# voice_caller.net
KiCad netlist of a schematic drawn in EAGLE
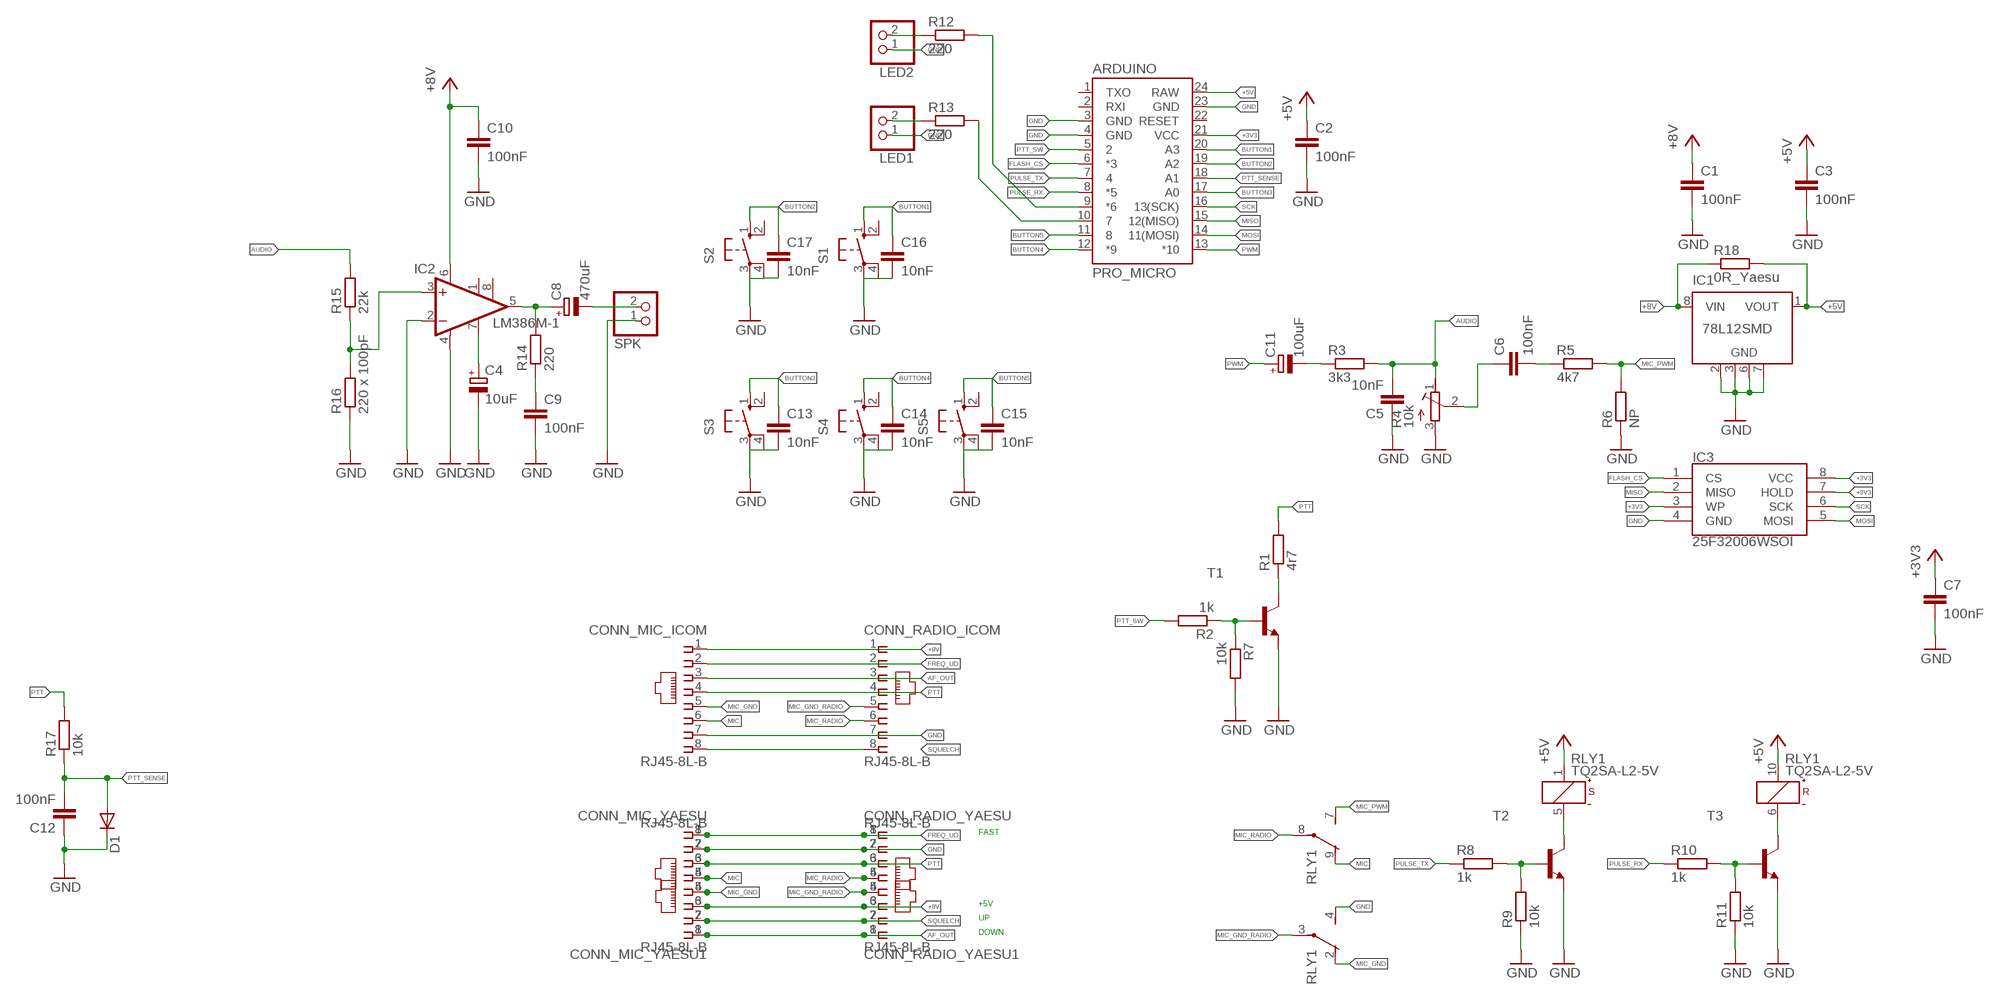
[diagram p0: schematic, sheet 1]

(export (version "E")
  (design (tool "Eeschema 10.0.6"))
  (components
    (comp (ref "ARDUINO")
      (value "PRO_MICRO")
      (footprint "eagle-import:SPARKFUN_PRO_MICRO")
      (libsource (lib "eagle-import") (part "SPARKFUN_PRO_MICRO"))
    )
    (comp (ref "C1")
      (value "100nF")
      (footprint "eagle-import:C1206K")
      (libsource (lib "eagle-import") (part "C-EUC1206K"))
    )
    (comp (ref "C2")
      (value "100nF")
      (footprint "eagle-import:C1206K")
      (libsource (lib "eagle-import") (part "C-EUC1206K"))
    )
    (comp (ref "C3")
      (value "100nF")
      (footprint "eagle-import:C1206K")
      (libsource (lib "eagle-import") (part "C-EUC1206K"))
    )
    (comp (ref "C4")
      (value "10uF")
      (footprint "eagle-import:E2,5-6")
      (libsource (lib "eagle-import") (part "CPOL-EUE2.5-6"))
    )
    (comp (ref "C5")
      (value "10nF")
      (footprint "eagle-import:C1206K")
      (libsource (lib "eagle-import") (part "C-EUC1206K"))
    )
    (comp (ref "C6")
      (value "100nF")
      (footprint "eagle-import:C1206K")
      (libsource (lib "eagle-import") (part "C-EUC1206K"))
    )
    (comp (ref "C7")
      (value "100nF")
      (footprint "eagle-import:C1206K")
      (libsource (lib "eagle-import") (part "C-EUC1206K"))
    )
    (comp (ref "C8")
      (value "470uF")
      (footprint "eagle-import:E2,5-6")
      (libsource (lib "eagle-import") (part "CPOL-EUE2.5-6"))
    )
    (comp (ref "C9")
      (value "100nF")
      (footprint "eagle-import:C1206K")
      (libsource (lib "eagle-import") (part "C-EUC1206K"))
    )
    (comp (ref "C10")
      (value "100nF")
      (footprint "eagle-import:C1206K")
      (libsource (lib "eagle-import") (part "C-EUC1206K"))
    )
    (comp (ref "C11")
      (value "100uF")
      (footprint "eagle-import:E2,5-6")
      (libsource (lib "eagle-import") (part "CPOL-EUE2.5-6"))
    )
    (comp (ref "C12")
      (value "100nF")
      (footprint "eagle-import:C1206K")
      (libsource (lib "eagle-import") (part "C-EUC1206K"))
    )
    (comp (ref "C13")
      (value "10nF")
      (footprint "eagle-import:C1206K")
      (libsource (lib "eagle-import") (part "C-EUC1206K"))
    )
    (comp (ref "C14")
      (value "10nF")
      (footprint "eagle-import:C1206K")
      (libsource (lib "eagle-import") (part "C-EUC1206K"))
    )
    (comp (ref "C15")
      (value "10nF")
      (footprint "eagle-import:C1206K")
      (libsource (lib "eagle-import") (part "C-EUC1206K"))
    )
    (comp (ref "C16")
      (value "10nF")
      (footprint "eagle-import:C1206K")
      (libsource (lib "eagle-import") (part "C-EUC1206K"))
    )
    (comp (ref "C17")
      (value "10nF")
      (footprint "eagle-import:C1206K")
      (libsource (lib "eagle-import") (part "C-EUC1206K"))
    )
    (comp (ref "CONN_MIC_ICOM")
      (value "RJ45-8L-B")
      (footprint "eagle-import:RJ45-NO-SHIELD")
      (fields (field (name "MF") "TYCO ELECTRONICS"))
      (libsource (lib "eagle-import") (part "RJ45-8L-B"))
    )
    (comp (ref "CONN_MIC_YAESU")
      (value "RJ45-8L-B")
      (footprint "eagle-import:RJ45-NO-SHIELD")
      (fields (field (name "MF") "TYCO ELECTRONICS"))
      (libsource (lib "eagle-import") (part "RJ45-8L-B"))
    )
    (comp (ref "CONN_MIC_YAESU1")
      (value "RJ45-8L-B")
      (footprint "eagle-import:RJ45-NO-SHIELD")
      (fields (field (name "MF") "TYCO ELECTRONICS"))
      (libsource (lib "eagle-import") (part "RJ45-8L-B"))
    )
    (comp (ref "CONN_RADIO_ICOM")
      (value "RJ45-8L-B")
      (footprint "eagle-import:RJ45-NO-SHIELD")
      (fields (field (name "MF") "TYCO ELECTRONICS"))
      (libsource (lib "eagle-import") (part "RJ45-8L-B"))
    )
    (comp (ref "CONN_RADIO_YAESU")
      (value "RJ45-8L-B")
      (footprint "eagle-import:RJ45-NO-SHIELD")
      (fields (field (name "MF") "TYCO ELECTRONICS"))
      (libsource (lib "eagle-import") (part "RJ45-8L-B"))
    )
    (comp (ref "CONN_RADIO_YAESU1")
      (value "RJ45-8L-B")
      (footprint "eagle-import:RJ45-NO-SHIELD")
      (fields (field (name "MF") "TYCO ELECTRONICS"))
      (libsource (lib "eagle-import") (part "RJ45-8L-B"))
    )
    (comp (ref "D1")
      (value "DIODE-SOD80C")
      (footprint "eagle-import:SOD80C")
      (libsource (lib "eagle-import") (part "DIODE-SOD80C"))
    )
    (comp (ref "IC1")
      (value "78L12SMD")
      (footprint "eagle-import:SO08")
      (libsource (lib "eagle-import") (part "78LSMD12"))
    )
    (comp (ref "IC2")
      (value "LM386M-1")
      (footprint "eagle-import:SO08")
      (libsource (lib "eagle-import") (part "LM386?-M1"))
    )
    (comp (ref "IC3")
      (value "25F32006WSOI")
      (footprint "eagle-import:SO08-EIAJ")
      (libsource (lib "eagle-import") (part "SPI_FLASH-X25XXSMD1"))
    )
    (comp (ref "LED1")
      (value "PINHD-1X2")
      (footprint "eagle-import:1X02")
      (libsource (lib "eagle-import") (part "PINHD-1X2"))
    )
    (comp (ref "LED2")
      (value "PINHD-1X2")
      (footprint "eagle-import:1X02")
      (libsource (lib "eagle-import") (part "PINHD-1X2"))
    )
    (comp (ref "R1")
      (value "4r7")
      (footprint "eagle-import:M1206")
      (libsource (lib "eagle-import") (part "R-EU_M1206"))
    )
    (comp (ref "R2")
      (value "1k")
      (footprint "eagle-import:M1206")
      (libsource (lib "eagle-import") (part "R-EU_M1206"))
    )
    (comp (ref "R3")
      (value "3k3")
      (footprint "eagle-import:M1206")
      (libsource (lib "eagle-import") (part "R-EU_M1206"))
    )
    (comp (ref "R4")
      (value "10k")
      (footprint "eagle-import:RTRIMT93XB")
      (libsource (lib "eagle-import") (part "R-TRIMMT93XB"))
    )
    (comp (ref "R5")
      (value "4k7")
      (footprint "eagle-import:M1206")
      (libsource (lib "eagle-import") (part "R-EU_M1206"))
    )
    (comp (ref "R6")
      (value "NP")
      (footprint "eagle-import:M1206")
      (libsource (lib "eagle-import") (part "R-EU_M1206"))
    )
    (comp (ref "R7")
      (value "10k")
      (footprint "eagle-import:M1206")
      (libsource (lib "eagle-import") (part "R-EU_M1206"))
    )
    (comp (ref "R8")
      (value "1k")
      (footprint "eagle-import:M1206")
      (libsource (lib "eagle-import") (part "R-EU_M1206"))
    )
    (comp (ref "R9")
      (value "10k")
      (footprint "eagle-import:M1206")
      (libsource (lib "eagle-import") (part "R-EU_M1206"))
    )
    (comp (ref "R10")
      (value "1k")
      (footprint "eagle-import:M1206")
      (libsource (lib "eagle-import") (part "R-EU_M1206"))
    )
    (comp (ref "R11")
      (value "10k")
      (footprint "eagle-import:M1206")
      (libsource (lib "eagle-import") (part "R-EU_M1206"))
    )
    (comp (ref "R12")
      (value "220")
      (footprint "eagle-import:M1206")
      (libsource (lib "eagle-import") (part "R-EU_M1206"))
    )
    (comp (ref "R13")
      (value "220")
      (footprint "eagle-import:M1206")
      (libsource (lib "eagle-import") (part "R-EU_M1206"))
    )
    (comp (ref "R14")
      (value "220")
      (footprint "eagle-import:M1206")
      (libsource (lib "eagle-import") (part "R-EU_M1206"))
    )
    (comp (ref "R15")
      (value "22k")
      (footprint "eagle-import:M1206")
      (libsource (lib "eagle-import") (part "R-EU_M1206"))
    )
    (comp (ref "R16")
      (value "220 x 100pF")
      (footprint "eagle-import:M1206")
      (libsource (lib "eagle-import") (part "R-EU_M1206"))
    )
    (comp (ref "R17")
      (value "10k")
      (footprint "eagle-import:M1206")
      (libsource (lib "eagle-import") (part "R-EU_M1206"))
    )
    (comp (ref "R18")
      (value "0R_Yaesu")
      (footprint "eagle-import:M1206")
      (libsource (lib "eagle-import") (part "R-EU_M1206"))
    )
    (comp (ref "RLY1")
      (value "TQ2SA-L2-5V")
      (footprint "eagle-import:TQ-SA")
      (fields (field (name "MF") "AROMAT/ MATSUSHITA"))
      (libsource (lib "eagle-import") (part "TQ2?-L2-SA5V"))
    )
    (comp (ref "S1")
      (value "10-XX")
      (footprint "eagle-import:B3F-10XX")
      (fields (field (name "MPN") "B3F-1000"))
      (libsource (lib "eagle-import") (part "10-XX"))
    )
    (comp (ref "S2")
      (value "10-XX")
      (footprint "eagle-import:B3F-10XX")
      (fields (field (name "MPN") "B3F-1000"))
      (libsource (lib "eagle-import") (part "10-XX"))
    )
    (comp (ref "S3")
      (value "10-XX")
      (footprint "eagle-import:B3F-10XX")
      (fields (field (name "MPN") "B3F-1000"))
      (libsource (lib "eagle-import") (part "10-XX"))
    )
    (comp (ref "S4")
      (value "10-XX")
      (footprint "eagle-import:B3F-10XX")
      (fields (field (name "MPN") "B3F-1000"))
      (libsource (lib "eagle-import") (part "10-XX"))
    )
    (comp (ref "S5")
      (value "10-XX")
      (footprint "eagle-import:B3F-10XX")
      (fields (field (name "MPN") "B3F-1000"))
      (libsource (lib "eagle-import") (part "10-XX"))
    )
    (comp (ref "SPK")
      (value "PINHD-1X2")
      (footprint "eagle-import:1X02")
      (libsource (lib "eagle-import") (part "PINHD-1X2"))
    )
    (comp (ref "T1")
      (value "MMBT3904LT1-NPN-SOT23-BEC")
      (footprint "eagle-import:SOT23-BEC")
      (libsource (lib "eagle-import") (part "-NPN-SOT23-BECMMBT3904LT1"))
    )
    (comp (ref "T2")
      (value "MMBT3904LT1-NPN-SOT23-BEC")
      (footprint "eagle-import:SOT23-BEC")
      (libsource (lib "eagle-import") (part "-NPN-SOT23-BECMMBT3904LT1"))
    )
    (comp (ref "T3")
      (value "MMBT3904LT1-NPN-SOT23-BEC")
      (footprint "eagle-import:SOT23-BEC")
      (libsource (lib "eagle-import") (part "-NPN-SOT23-BECMMBT3904LT1"))
    )
  )
  (nets
    (net (code "1") (name "+3V3") (class "Default")
      (node (ref "ARDUINO") (pin "21") (pinfunction "VCC_21") (pintype "power_in"))
      (node (ref "C7") (pin "1") (pinfunction "1_1") (pintype "passive"))
      (node (ref "IC3") (pin "3") (pinfunction "WP_3") (pintype "bidirectional"))
      (node (ref "IC3") (pin "7") (pinfunction "HOLD_7") (pintype "bidirectional"))
      (node (ref "IC3") (pin "8") (pinfunction "VCC_8") (pintype "power_in"))
    )
    (net (code "2") (name "+5V") (class "Default")
      (node (ref "ARDUINO") (pin "24") (pinfunction "RAW_24") (pintype "power_in"))
      (node (ref "C2") (pin "1") (pinfunction "1_1") (pintype "passive"))
      (node (ref "C3") (pin "1") (pinfunction "1_1") (pintype "passive"))
      (node (ref "IC1") (pin "1") (pinfunction "VOUT_1") (pintype "output"))
      (node (ref "R18") (pin "2") (pinfunction "2_2") (pintype "passive"))
      (node (ref "RLY1") (pin "1") (pinfunction "+_1") (pintype "passive"))
      (node (ref "RLY1") (pin "10") (pinfunction "+_10") (pintype "passive"))
    )
    (net (code "3") (name "+8V") (class "Default")
      (node (ref "C1") (pin "1") (pinfunction "1_1") (pintype "passive"))
      (node (ref "C10") (pin "1") (pinfunction "1_1") (pintype "passive"))
      (node (ref "CONN_MIC_ICOM") (pin "1") (pinfunction "1_1") (pintype "passive"))
      (node (ref "CONN_MIC_YAESU") (pin "6") (pinfunction "6_6") (pintype "passive"))
      (node (ref "CONN_MIC_YAESU1") (pin "3") (pinfunction "3_3") (pintype "passive"))
      (node (ref "CONN_RADIO_ICOM") (pin "1") (pinfunction "1_1") (pintype "passive"))
      (node (ref "CONN_RADIO_YAESU") (pin "6") (pinfunction "6_6") (pintype "passive"))
      (node (ref "CONN_RADIO_YAESU1") (pin "3") (pinfunction "3_3") (pintype "passive"))
      (node (ref "IC1") (pin "8") (pinfunction "VIN_8") (pintype "passive"))
      (node (ref "IC2") (pin "6") (pinfunction "VS_6") (pintype "power_in"))
      (node (ref "R18") (pin "1") (pinfunction "1_1") (pintype "passive"))
    )
    (net (code "4") (name "AF_OUT") (class "Default")
      (node (ref "CONN_MIC_ICOM") (pin "3") (pinfunction "3_3") (pintype "passive"))
      (node (ref "CONN_MIC_YAESU") (pin "8") (pinfunction "8_8") (pintype "passive"))
      (node (ref "CONN_MIC_YAESU1") (pin "1") (pinfunction "1_1") (pintype "passive"))
      (node (ref "CONN_RADIO_ICOM") (pin "3") (pinfunction "3_3") (pintype "passive"))
      (node (ref "CONN_RADIO_YAESU") (pin "8") (pinfunction "8_8") (pintype "passive"))
      (node (ref "CONN_RADIO_YAESU1") (pin "1") (pinfunction "1_1") (pintype "passive"))
    )
    (net (code "5") (name "AUDIO") (class "Default")
      (node (ref "C5") (pin "2") (pinfunction "2_2") (pintype "passive"))
      (node (ref "R15") (pin "2") (pinfunction "2_2") (pintype "passive"))
      (node (ref "R3") (pin "2") (pinfunction "2_2") (pintype "passive"))
      (node (ref "R4") (pin "1") (pinfunction "E_1") (pintype "passive"))
    )
    (net (code "6") (name "BUTTON1") (class "Default")
      (node (ref "ARDUINO") (pin "20") (pinfunction "A3_20") (pintype "bidirectional"))
      (node (ref "C16") (pin "1") (pinfunction "1_1") (pintype "passive"))
      (node (ref "S1") (pin "1") (pinfunction "S_1") (pintype "passive"))
    )
    (net (code "7") (name "BUTTON2") (class "Default")
      (node (ref "ARDUINO") (pin "19") (pinfunction "A2_19") (pintype "bidirectional"))
      (node (ref "C17") (pin "1") (pinfunction "1_1") (pintype "passive"))
      (node (ref "S2") (pin "1") (pinfunction "S_1") (pintype "passive"))
    )
    (net (code "8") (name "BUTTON3") (class "Default")
      (node (ref "ARDUINO") (pin "17") (pinfunction "A0_17") (pintype "bidirectional"))
      (node (ref "C13") (pin "1") (pinfunction "1_1") (pintype "passive"))
      (node (ref "S3") (pin "1") (pinfunction "S_1") (pintype "passive"))
    )
    (net (code "9") (name "BUTTON4") (class "Default")
      (node (ref "ARDUINO") (pin "12") (pinfunction "*9_12") (pintype "bidirectional"))
      (node (ref "C14") (pin "1") (pinfunction "1_1") (pintype "passive"))
      (node (ref "S4") (pin "1") (pinfunction "S_1") (pintype "passive"))
    )
    (net (code "10") (name "BUTTON5") (class "Default")
      (node (ref "ARDUINO") (pin "11") (pinfunction "8_11") (pintype "bidirectional"))
      (node (ref "C15") (pin "1") (pinfunction "1_1") (pintype "passive"))
      (node (ref "S5") (pin "1") (pinfunction "S_1") (pintype "passive"))
    )
    (net (code "11") (name "FLASH_CS") (class "Default")
      (node (ref "ARDUINO") (pin "6") (pinfunction "*3_6") (pintype "bidirectional"))
      (node (ref "IC3") (pin "1") (pinfunction "CS_1") (pintype "bidirectional"))
    )
    (net (code "12") (name "FREQ_UD") (class "Default")
      (node (ref "CONN_MIC_ICOM") (pin "2") (pinfunction "2_2") (pintype "passive"))
      (node (ref "CONN_MIC_YAESU") (pin "1") (pinfunction "1_1") (pintype "passive"))
      (node (ref "CONN_MIC_YAESU1") (pin "8") (pinfunction "8_8") (pintype "passive"))
      (node (ref "CONN_RADIO_ICOM") (pin "2") (pinfunction "2_2") (pintype "passive"))
      (node (ref "CONN_RADIO_YAESU") (pin "1") (pinfunction "1_1") (pintype "passive"))
      (node (ref "CONN_RADIO_YAESU1") (pin "8") (pinfunction "8_8") (pintype "passive"))
    )
    (net (code "13") (name "GND") (class "Default")
      (node (ref "ARDUINO") (pin "23") (pinfunction "GND_23") (pintype "power_in"))
      (node (ref "ARDUINO") (pin "3") (pinfunction "GND_3") (pintype "power_in"))
      (node (ref "ARDUINO") (pin "4") (pinfunction "GND_4") (pintype "power_in"))
      (node (ref "C1") (pin "2") (pinfunction "2_2") (pintype "passive"))
      (node (ref "C10") (pin "2") (pinfunction "2_2") (pintype "passive"))
      (node (ref "C12") (pin "1") (pinfunction "1_1") (pintype "passive"))
      (node (ref "C13") (pin "2") (pinfunction "2_2") (pintype "passive"))
      (node (ref "C14") (pin "2") (pinfunction "2_2") (pintype "passive"))
      (node (ref "C15") (pin "2") (pinfunction "2_2") (pintype "passive"))
      (node (ref "C16") (pin "2") (pinfunction "2_2") (pintype "passive"))
      (node (ref "C17") (pin "2") (pinfunction "2_2") (pintype "passive"))
      (node (ref "C2") (pin "2") (pinfunction "2_2") (pintype "passive"))
      (node (ref "C3") (pin "2") (pinfunction "2_2") (pintype "passive"))
      (node (ref "C4") (pin "-") (pinfunction "-_-") (pintype "passive"))
      (node (ref "C5") (pin "1") (pinfunction "1_1") (pintype "passive"))
      (node (ref "C7") (pin "2") (pinfunction "2_2") (pintype "passive"))
      (node (ref "C9") (pin "2") (pinfunction "2_2") (pintype "passive"))
      (node (ref "CONN_MIC_ICOM") (pin "7") (pinfunction "7_7") (pintype "passive"))
      (node (ref "CONN_MIC_YAESU") (pin "2") (pinfunction "2_2") (pintype "passive"))
      (node (ref "CONN_MIC_YAESU1") (pin "7") (pinfunction "7_7") (pintype "passive"))
      (node (ref "CONN_RADIO_ICOM") (pin "7") (pinfunction "7_7") (pintype "passive"))
      (node (ref "CONN_RADIO_YAESU") (pin "2") (pinfunction "2_2") (pintype "passive"))
      (node (ref "CONN_RADIO_YAESU1") (pin "7") (pinfunction "7_7") (pintype "passive"))
      (node (ref "D1") (pin "C") (pinfunction "C_C") (pintype "passive"))
      (node (ref "IC1") (pin "2") (pinfunction "GND_2") (pintype "power_in"))
      (node (ref "IC1") (pin "3") (pinfunction "GND_3") (pintype "power_in"))
      (node (ref "IC1") (pin "6") (pinfunction "GND_6") (pintype "power_in"))
      (node (ref "IC1") (pin "7") (pinfunction "GND_7") (pintype "power_in"))
      (node (ref "IC2") (pin "2") (pinfunction "-IN_2") (pintype "input"))
      (node (ref "IC2") (pin "4") (pinfunction "GND_4") (pintype "power_in"))
      (node (ref "IC3") (pin "4") (pinfunction "GND_4") (pintype "power_in"))
      (node (ref "LED1") (pin "1") (pinfunction "1_1") (pintype "passive"))
      (node (ref "LED2") (pin "1") (pinfunction "1_1") (pintype "passive"))
      (node (ref "R11") (pin "1") (pinfunction "1_1") (pintype "passive"))
      (node (ref "R16") (pin "1") (pinfunction "1_1") (pintype "passive"))
      (node (ref "R4") (pin "3") (pinfunction "A_3") (pintype "passive"))
      (node (ref "R6") (pin "1") (pinfunction "1_1") (pintype "passive"))
      (node (ref "R7") (pin "2") (pinfunction "2_2") (pintype "passive"))
      (node (ref "R9") (pin "1") (pinfunction "1_1") (pintype "passive"))
      (node (ref "RLY1") (pin "4") (pinfunction "S_4") (pintype "passive"))
      (node (ref "S1") (pin "3") (pinfunction "P_3") (pintype "passive"))
      (node (ref "S1") (pin "4") (pinfunction "P1_4") (pintype "passive"))
      (node (ref "S2") (pin "3") (pinfunction "P_3") (pintype "passive"))
      (node (ref "S2") (pin "4") (pinfunction "P1_4") (pintype "passive"))
      (node (ref "S3") (pin "3") (pinfunction "P_3") (pintype "passive"))
      (node (ref "S3") (pin "4") (pinfunction "P1_4") (pintype "passive"))
      (node (ref "S4") (pin "3") (pinfunction "P_3") (pintype "passive"))
      (node (ref "S4") (pin "4") (pinfunction "P1_4") (pintype "passive"))
      (node (ref "S5") (pin "3") (pinfunction "P_3") (pintype "passive"))
      (node (ref "S5") (pin "4") (pinfunction "P1_4") (pintype "passive"))
      (node (ref "SPK") (pin "1") (pinfunction "1_1") (pintype "passive"))
      (node (ref "T1") (pin "E") (pinfunction "E_E") (pintype "passive"))
      (node (ref "T2") (pin "E") (pinfunction "E_E") (pintype "passive"))
      (node (ref "T3") (pin "E") (pinfunction "E_E") (pintype "passive"))
    )
    (net (code "14") (name "MIC") (class "Default")
      (node (ref "CONN_MIC_ICOM") (pin "6") (pinfunction "6_6") (pintype "passive"))
      (node (ref "CONN_MIC_YAESU") (pin "4") (pinfunction "4_4") (pintype "passive"))
      (node (ref "CONN_MIC_YAESU1") (pin "5") (pinfunction "5_5") (pintype "passive"))
      (node (ref "RLY1") (pin "9") (pinfunction "O_9") (pintype "passive"))
    )
    (net (code "15") (name "MIC_GND") (class "Default")
      (node (ref "CONN_MIC_ICOM") (pin "5") (pinfunction "5_5") (pintype "passive"))
      (node (ref "CONN_MIC_YAESU") (pin "5") (pinfunction "5_5") (pintype "passive"))
      (node (ref "CONN_MIC_YAESU1") (pin "4") (pinfunction "4_4") (pintype "passive"))
      (node (ref "RLY1") (pin "2") (pinfunction "O_2") (pintype "passive"))
    )
    (net (code "16") (name "MIC_GND_RADIO") (class "Default")
      (node (ref "CONN_RADIO_ICOM") (pin "5") (pinfunction "5_5") (pintype "passive"))
      (node (ref "CONN_RADIO_YAESU") (pin "5") (pinfunction "5_5") (pintype "passive"))
      (node (ref "CONN_RADIO_YAESU1") (pin "4") (pinfunction "4_4") (pintype "passive"))
      (node (ref "RLY1") (pin "3") (pinfunction "P_3") (pintype "passive"))
    )
    (net (code "17") (name "MIC_PWM") (class "Default")
      (node (ref "R5") (pin "2") (pinfunction "2_2") (pintype "passive"))
      (node (ref "R6") (pin "2") (pinfunction "2_2") (pintype "passive"))
      (node (ref "RLY1") (pin "7") (pinfunction "S_7") (pintype "passive"))
    )
    (net (code "18") (name "MIC_RADIO") (class "Default")
      (node (ref "CONN_RADIO_ICOM") (pin "6") (pinfunction "6_6") (pintype "passive"))
      (node (ref "CONN_RADIO_YAESU") (pin "4") (pinfunction "4_4") (pintype "passive"))
      (node (ref "CONN_RADIO_YAESU1") (pin "5") (pinfunction "5_5") (pintype "passive"))
      (node (ref "RLY1") (pin "8") (pinfunction "P_8") (pintype "passive"))
    )
    (net (code "19") (name "MISO") (class "Default")
      (node (ref "ARDUINO") (pin "15") (pinfunction "12(MISO)_15") (pintype "bidirectional"))
      (node (ref "IC3") (pin "2") (pinfunction "MISO_2") (pintype "bidirectional"))
    )
    (net (code "20") (name "MOSI") (class "Default")
      (node (ref "ARDUINO") (pin "14") (pinfunction "11(MOSI)_14") (pintype "bidirectional"))
      (node (ref "IC3") (pin "5") (pinfunction "MOSI_5") (pintype "bidirectional"))
    )
    (net (code "21") (name "Net-(ARDUINO-*6)") (class "Default")
      (node (ref "ARDUINO") (pin "9") (pinfunction "*6_9") (pintype "bidirectional"))
      (node (ref "R12") (pin "2") (pinfunction "2_2") (pintype "passive"))
    )
    (net (code "22") (name "Net-(ARDUINO-7)") (class "Default")
      (node (ref "ARDUINO") (pin "10") (pinfunction "7_10") (pintype "bidirectional"))
      (node (ref "R13") (pin "2") (pinfunction "2_2") (pintype "passive"))
    )
    (net (code "23") (name "Net-(C6-Pad2)") (class "Default")
      (node (ref "C6") (pin "2") (pinfunction "2_2") (pintype "passive"))
      (node (ref "R5") (pin "1") (pinfunction "1_1") (pintype "passive"))
    )
    (net (code "24") (name "Net-(C8-Pad-)") (class "Default")
      (node (ref "C8") (pin "-") (pinfunction "-_-") (pintype "passive"))
      (node (ref "SPK") (pin "2") (pinfunction "2_2") (pintype "passive"))
    )
    (net (code "25") (name "Net-(C9-Pad1)") (class "Default")
      (node (ref "C9") (pin "1") (pinfunction "1_1") (pintype "passive"))
      (node (ref "R14") (pin "1") (pinfunction "1_1") (pintype "passive"))
    )
    (net (code "26") (name "Net-(C11-Pad-)") (class "Default")
      (node (ref "C11") (pin "-") (pinfunction "-_-") (pintype "passive"))
      (node (ref "R3") (pin "1") (pinfunction "1_1") (pintype "passive"))
    )
    (net (code "27") (name "Net-(IC2-+IN)") (class "Default")
      (node (ref "IC2") (pin "3") (pinfunction "+IN_3") (pintype "input"))
      (node (ref "R15") (pin "1") (pinfunction "1_1") (pintype "passive"))
      (node (ref "R16") (pin "2") (pinfunction "2_2") (pintype "passive"))
    )
    (net (code "28") (name "Net-(IC2-BYPASS)") (class "Default")
      (node (ref "C4") (pin "+") (pinfunction "+_+") (pintype "passive"))
      (node (ref "IC2") (pin "7") (pinfunction "BYPASS_7") (pintype "passive"))
    )
    (net (code "29") (name "Net-(IC2-OUT)") (class "Default")
      (node (ref "C8") (pin "+") (pinfunction "+_+") (pintype "passive"))
      (node (ref "IC2") (pin "5") (pinfunction "OUT_5") (pintype "output"))
      (node (ref "R14") (pin "2") (pinfunction "2_2") (pintype "passive"))
    )
    (net (code "30") (name "Net-(LED1-Pad2)") (class "Default")
      (node (ref "LED1") (pin "2") (pinfunction "2_2") (pintype "passive"))
      (node (ref "R13") (pin "1") (pinfunction "1_1") (pintype "passive"))
    )
    (net (code "31") (name "Net-(LED2-Pad2)") (class "Default")
      (node (ref "LED2") (pin "2") (pinfunction "2_2") (pintype "passive"))
      (node (ref "R12") (pin "1") (pinfunction "1_1") (pintype "passive"))
    )
    (net (code "32") (name "Net-(R1-Pad1)") (class "Default")
      (node (ref "R1") (pin "1") (pinfunction "1_1") (pintype "passive"))
      (node (ref "T1") (pin "C") (pinfunction "C_C") (pintype "passive"))
    )
    (net (code "33") (name "Net-(R2-Pad1)") (class "Default")
      (node (ref "R2") (pin "1") (pinfunction "1_1") (pintype "passive"))
      (node (ref "R7") (pin "1") (pinfunction "1_1") (pintype "passive"))
      (node (ref "T1") (pin "B") (pinfunction "B_B") (pintype "passive"))
    )
    (net (code "34") (name "Net-(R4-S)") (class "Default")
      (node (ref "C6") (pin "1") (pinfunction "1_1") (pintype "passive"))
      (node (ref "R4") (pin "2") (pinfunction "S_2") (pintype "passive"))
    )
    (net (code "35") (name "Net-(R8-Pad2)") (class "Default")
      (node (ref "R8") (pin "2") (pinfunction "2_2") (pintype "passive"))
      (node (ref "R9") (pin "2") (pinfunction "2_2") (pintype "passive"))
      (node (ref "T2") (pin "B") (pinfunction "B_B") (pintype "passive"))
    )
    (net (code "36") (name "Net-(R10-Pad2)") (class "Default")
      (node (ref "R10") (pin "2") (pinfunction "2_2") (pintype "passive"))
      (node (ref "R11") (pin "2") (pinfunction "2_2") (pintype "passive"))
      (node (ref "T3") (pin "B") (pinfunction "B_B") (pintype "passive"))
    )
    (net (code "37") (name "Net-(RLY1C--)") (class "Default")
      (node (ref "RLY1") (pin "6") (pinfunction "-_6") (pintype "passive"))
      (node (ref "T3") (pin "C") (pinfunction "C_C") (pintype "passive"))
    )
    (net (code "38") (name "Net-(RLY1D--)") (class "Default")
      (node (ref "RLY1") (pin "5") (pinfunction "-_5") (pintype "passive"))
      (node (ref "T2") (pin "C") (pinfunction "C_C") (pintype "passive"))
    )
    (net (code "39") (name "PTT") (class "Default")
      (node (ref "CONN_MIC_ICOM") (pin "4") (pinfunction "4_4") (pintype "passive"))
      (node (ref "CONN_MIC_YAESU") (pin "3") (pinfunction "3_3") (pintype "passive"))
      (node (ref "CONN_MIC_YAESU1") (pin "6") (pinfunction "6_6") (pintype "passive"))
      (node (ref "CONN_RADIO_ICOM") (pin "4") (pinfunction "4_4") (pintype "passive"))
      (node (ref "CONN_RADIO_YAESU") (pin "3") (pinfunction "3_3") (pintype "passive"))
      (node (ref "CONN_RADIO_YAESU1") (pin "6") (pinfunction "6_6") (pintype "passive"))
      (node (ref "R1") (pin "2") (pinfunction "2_2") (pintype "passive"))
      (node (ref "R17") (pin "2") (pinfunction "2_2") (pintype "passive"))
    )
    (net (code "40") (name "PTT_SENSE") (class "Default")
      (node (ref "ARDUINO") (pin "18") (pinfunction "A1_18") (pintype "bidirectional"))
      (node (ref "C12") (pin "2") (pinfunction "2_2") (pintype "passive"))
      (node (ref "D1") (pin "A") (pinfunction "A_A") (pintype "passive"))
      (node (ref "R17") (pin "1") (pinfunction "1_1") (pintype "passive"))
    )
    (net (code "41") (name "PTT_SW") (class "Default")
      (node (ref "ARDUINO") (pin "5") (pinfunction "2_5") (pintype "bidirectional"))
      (node (ref "R2") (pin "2") (pinfunction "2_2") (pintype "passive"))
    )
    (net (code "42") (name "PULSE_RX") (class "Default")
      (node (ref "ARDUINO") (pin "8") (pinfunction "*5_8") (pintype "bidirectional"))
      (node (ref "R10") (pin "1") (pinfunction "1_1") (pintype "passive"))
    )
    (net (code "43") (name "PULSE_TX") (class "Default")
      (node (ref "ARDUINO") (pin "7") (pinfunction "4_7") (pintype "bidirectional"))
      (node (ref "R8") (pin "1") (pinfunction "1_1") (pintype "passive"))
    )
    (net (code "44") (name "PWM") (class "Default")
      (node (ref "ARDUINO") (pin "13") (pinfunction "*10_13") (pintype "bidirectional"))
      (node (ref "C11") (pin "+") (pinfunction "+_+") (pintype "passive"))
    )
    (net (code "45") (name "SCK") (class "Default")
      (node (ref "ARDUINO") (pin "16") (pinfunction "13(SCK)_16") (pintype "bidirectional"))
      (node (ref "IC3") (pin "6") (pinfunction "SCK_6") (pintype "bidirectional"))
    )
    (net (code "46") (name "SQUELCH") (class "Default")
      (node (ref "CONN_MIC_ICOM") (pin "8") (pinfunction "8_8") (pintype "passive"))
      (node (ref "CONN_MIC_YAESU") (pin "7") (pinfunction "7_7") (pintype "passive"))
      (node (ref "CONN_MIC_YAESU1") (pin "2") (pinfunction "2_2") (pintype "passive"))
      (node (ref "CONN_RADIO_ICOM") (pin "8") (pinfunction "8_8") (pintype "passive"))
      (node (ref "CONN_RADIO_YAESU") (pin "7") (pinfunction "7_7") (pintype "passive"))
      (node (ref "CONN_RADIO_YAESU1") (pin "2") (pinfunction "2_2") (pintype "passive"))
    )
    (net (code "47") (name "unconnected-(ARDUINO-RESET-Pad22)") (class "Default")
      (node (ref "ARDUINO") (pin "22") (pinfunction "RESET_22") (pintype "bidirectional"))
    )
    (net (code "48") (name "unconnected-(ARDUINO-RXI-Pad2)") (class "Default")
      (node (ref "ARDUINO") (pin "2") (pinfunction "RXI_2") (pintype "bidirectional"))
    )
    (net (code "49") (name "unconnected-(ARDUINO-TXO-Pad1)") (class "Default")
      (node (ref "ARDUINO") (pin "1") (pinfunction "TXO_1") (pintype "bidirectional"))
    )
    (net (code "50") (name "unconnected-(IC2-GAIN-Pad1)") (class "Default")
      (node (ref "IC2") (pin "1") (pinfunction "GAIN_1") (pintype "passive"))
    )
    (net (code "51") (name "unconnected-(IC2-GAIN-Pad8)") (class "Default")
      (node (ref "IC2") (pin "8") (pinfunction "GAIN_8") (pintype "passive"))
    )
    (net (code "52") (name "unconnected-(S1-S1-Pad2)") (class "Default")
      (node (ref "S1") (pin "2") (pinfunction "S1_2") (pintype "passive"))
    )
    (net (code "53") (name "unconnected-(S2-S1-Pad2)") (class "Default")
      (node (ref "S2") (pin "2") (pinfunction "S1_2") (pintype "passive"))
    )
    (net (code "54") (name "unconnected-(S3-S1-Pad2)") (class "Default")
      (node (ref "S3") (pin "2") (pinfunction "S1_2") (pintype "passive"))
    )
    (net (code "55") (name "unconnected-(S4-S1-Pad2)") (class "Default")
      (node (ref "S4") (pin "2") (pinfunction "S1_2") (pintype "passive"))
    )
    (net (code "56") (name "unconnected-(S5-S1-Pad2)") (class "Default")
      (node (ref "S5") (pin "2") (pinfunction "S1_2") (pintype "passive"))
    )
  )
)
